# Panel.net
KiCad netlist of a schematic drawn in EAGLE
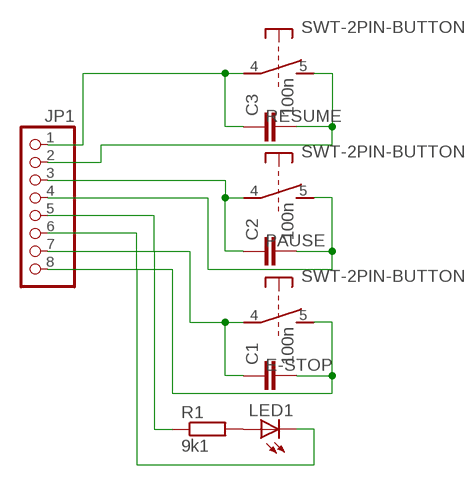
[diagram p0: schematic, sheet 1]

(export (version "E")
  (design (tool "Eeschema 10.0.6"))
  (components
    (comp (ref "C1")
      (value "100n")
      (footprint "eagle-import:C0805")
      (libsource (lib "eagle-import") (part "C-EUC0805"))
    )
    (comp (ref "C2")
      (value "100n")
      (footprint "eagle-import:C0805")
      (libsource (lib "eagle-import") (part "C-EUC0805"))
    )
    (comp (ref "C3")
      (value "100n")
      (footprint "eagle-import:C0805")
      (libsource (lib "eagle-import") (part "C-EUC0805"))
    )
    (comp (ref "E-STOP")
      (value "SWT-2PIN-BUTTON")
      (footprint "eagle-import:SWT-2-2PIN-WBUTTON")
      (libsource (lib "eagle-import") (part "SWT-2PIN-BUTTON"))
    )
    (comp (ref "JP1")
      (value "PINHD-1X8/90")
      (footprint "eagle-import:1X08_90")
      (libsource (lib "eagle-import") (part "PINHD-1X8/90"))
    )
    (comp (ref "LED1")
      (value "LED3MM")
      (footprint "eagle-import:LED3MM")
      (libsource (lib "eagle-import") (part "LED3MM"))
    )
    (comp (ref "PAUSE")
      (value "SWT-2PIN-BUTTON")
      (footprint "eagle-import:SWT-2-2PIN-WBUTTON")
      (libsource (lib "eagle-import") (part "SWT-2PIN-BUTTON"))
    )
    (comp (ref "R1")
      (value "9k1")
      (footprint "eagle-import:R0805")
      (libsource (lib "eagle-import") (part "R-EU_R0805"))
    )
    (comp (ref "RESUME")
      (value "SWT-2PIN-BUTTON")
      (footprint "eagle-import:SWT-2-2PIN-WBUTTON")
      (libsource (lib "eagle-import") (part "SWT-2PIN-BUTTON"))
    )
  )
  (nets
    (net (code "1") (name "Net-(E-STOP-2)") (class "Default")
      (node (ref "C1") (pin "1") (pinfunction "1_1") (pintype "passive"))
      (node (ref "E-STOP") (pin "4") (pinfunction "2_4") (pintype "passive"))
      (node (ref "JP1") (pin "7") (pinfunction "7_7") (pintype "passive"))
    )
    (net (code "2") (name "Net-(E-STOP-3)") (class "Default")
      (node (ref "C1") (pin "2") (pinfunction "2_2") (pintype "passive"))
      (node (ref "E-STOP") (pin "5") (pinfunction "3_5") (pintype "passive"))
      (node (ref "JP1") (pin "8") (pinfunction "8_8") (pintype "passive"))
    )
    (net (code "3") (name "Net-(JP1-Pad5)") (class "Default")
      (node (ref "JP1") (pin "5") (pinfunction "5_5") (pintype "passive"))
      (node (ref "R1") (pin "1") (pinfunction "1_1") (pintype "passive"))
    )
    (net (code "4") (name "Net-(LED1-C)") (class "Default")
      (node (ref "JP1") (pin "6") (pinfunction "6_6") (pintype "passive"))
      (node (ref "LED1") (pin "K") (pinfunction "C_K") (pintype "passive"))
    )
    (net (code "5") (name "Net-(LED1-PadA)") (class "Default")
      (node (ref "LED1") (pin "A") (pinfunction "A_A") (pintype "passive"))
      (node (ref "R1") (pin "2") (pinfunction "2_2") (pintype "passive"))
    )
    (net (code "6") (name "Net-(PAUSE-2)") (class "Default")
      (node (ref "C2") (pin "1") (pinfunction "1_1") (pintype "passive"))
      (node (ref "JP1") (pin "3") (pinfunction "3_3") (pintype "passive"))
      (node (ref "PAUSE") (pin "4") (pinfunction "2_4") (pintype "passive"))
    )
    (net (code "7") (name "Net-(PAUSE-3)") (class "Default")
      (node (ref "C2") (pin "2") (pinfunction "2_2") (pintype "passive"))
      (node (ref "JP1") (pin "4") (pinfunction "4_4") (pintype "passive"))
      (node (ref "PAUSE") (pin "5") (pinfunction "3_5") (pintype "passive"))
    )
    (net (code "8") (name "Net-(RESUME-2)") (class "Default")
      (node (ref "C3") (pin "1") (pinfunction "1_1") (pintype "passive"))
      (node (ref "JP1") (pin "1") (pinfunction "1_1") (pintype "passive"))
      (node (ref "RESUME") (pin "4") (pinfunction "2_4") (pintype "passive"))
    )
    (net (code "9") (name "Net-(RESUME-3)") (class "Default")
      (node (ref "C3") (pin "2") (pinfunction "2_2") (pintype "passive"))
      (node (ref "JP1") (pin "2") (pinfunction "2_2") (pintype "passive"))
      (node (ref "RESUME") (pin "5") (pinfunction "3_5") (pintype "passive"))
    )
  )
)
